# Sheet2.net
KiCad netlist of a schematic drawn in Altium Designer
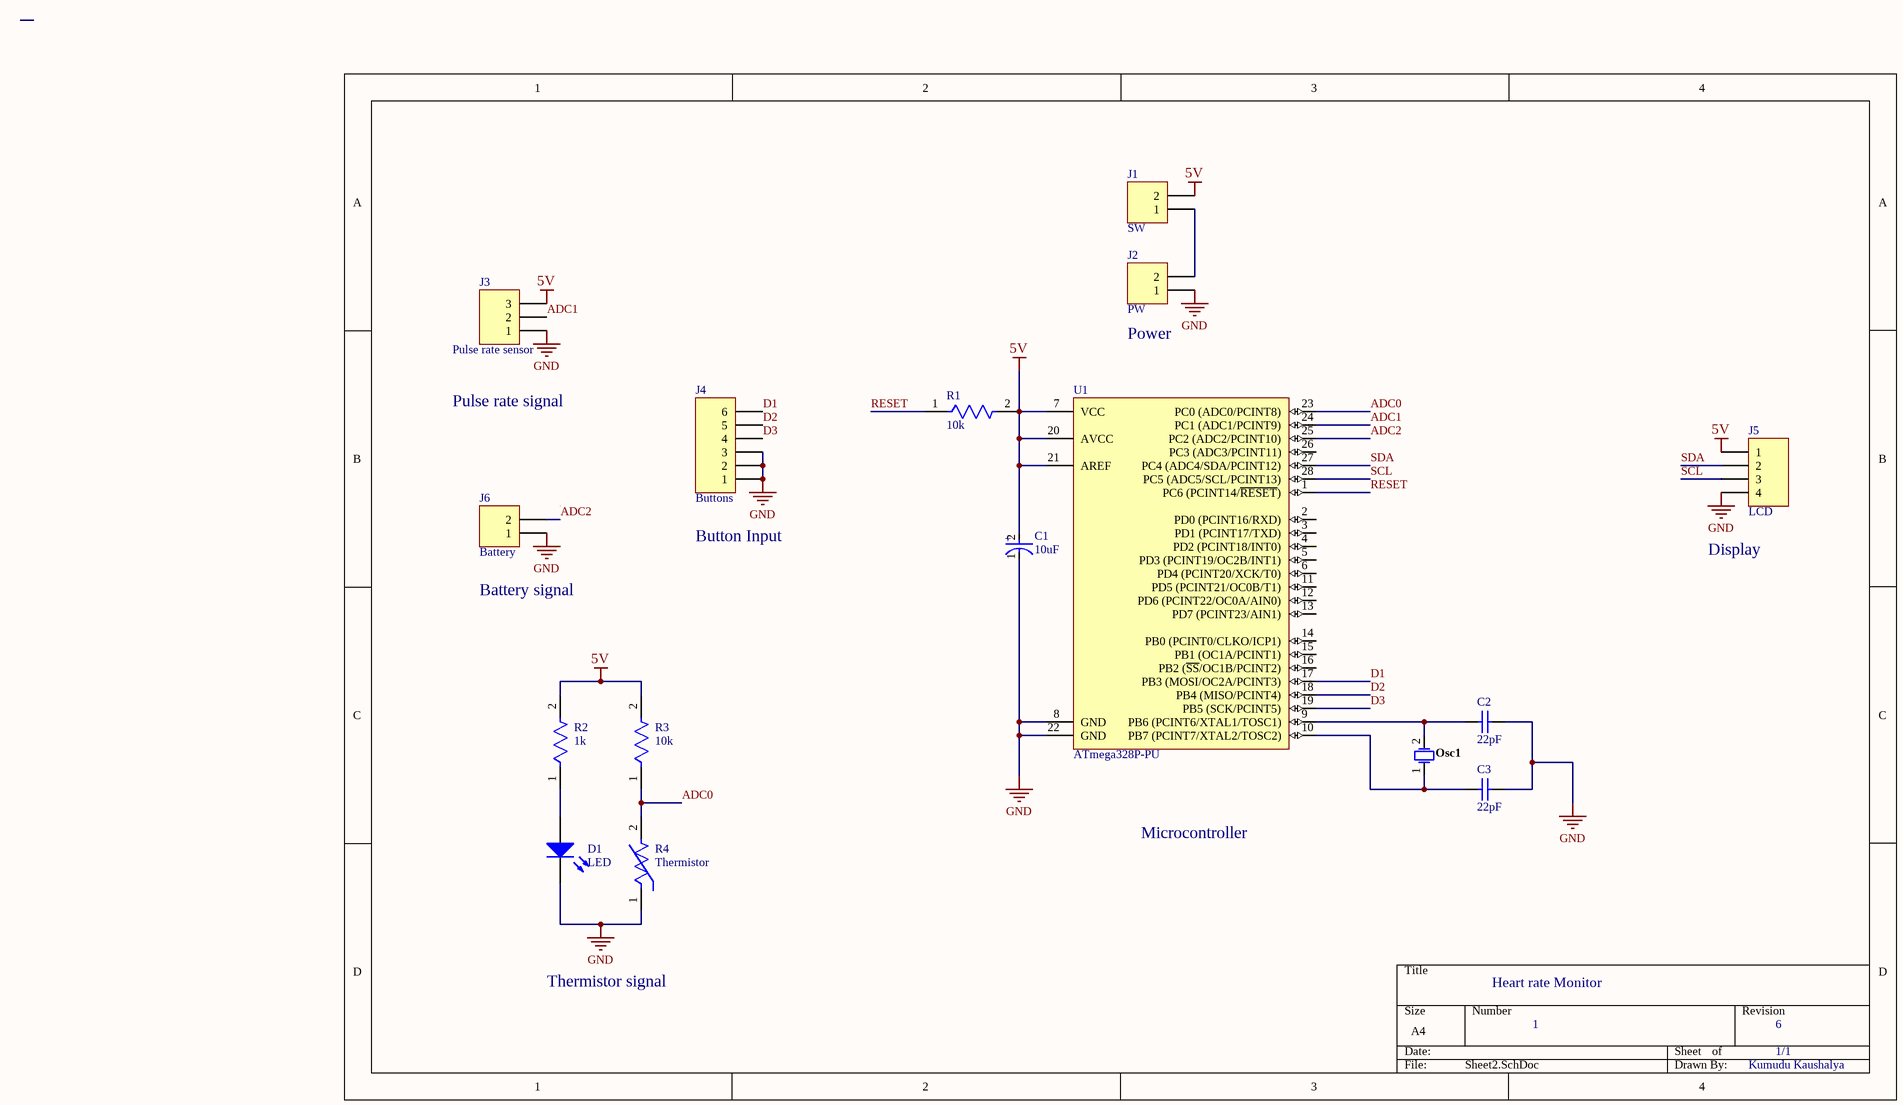
[diagram p0: Sheet2.SchDoc]

(export (version "E")
  (design (tool "Eeschema 10.0.6"))
  (components
    (comp (ref "C1")
      (value "10uF")
      (footprint "FP-RAD-TH-D_5_0_5-L_11_1-MFG")
      (description "Aluminum Electrolytic Capacitors (Radial Lead Type) 10uF ±20% 100V")
      (fields (field (name "VOLTAGE") "100V") (field (name "TOLERANCE") "20%"))
      (libsource (lib "Altium Content Vault") (part "a00bbbee19879c290e62620ae7e47b1"))
    )
    (comp (ref "C2")
      (value "22pF")
      (footprint "KEMT-C315-THT-2")
      (description "Capacitor, Ceramic, 22 pF, +/-10 %, 100 V, -55 to 125 degC, 2-Pin THD, RoHS, Bulk")
      (libsource (lib "Altium Content Vault") (part "CAP-NP-2"))
    )
    (comp (ref "C3")
      (value "22pF")
      (footprint "KEMT-C315-THT-2")
      (description "Capacitor, Ceramic, 22 pF, +/-10 %, 100 V, -55 to 125 degC, 2-Pin THD, RoHS, Bulk")
      (libsource (lib "Altium Content Vault") (part "CAP-NP-2"))
    )
    (comp (ref "D1")
      (value "LED")
      (footprint "LED-1")
      (description "Typical RED GaAs LED")
      (fields (field (name "PUBLISHER") "Altium Limited"))
      (libsource (lib "Miscellaneous Devices") (part "LED1"))
    )
    (comp (ref "J1")
      (value "SW")
      (footprint "HDR1X2")
      (description "Header, 2-Pin")
      (fields (field (name "PUBLISHER") "Altium Limited"))
      (libsource (lib "Miscellaneous Connectors") (part "Header 2"))
    )
    (comp (ref "J2")
      (value "PW")
      (footprint "HDR1X2")
      (description "Header, 2-Pin")
      (fields (field (name "PUBLISHER") "Altium Limited"))
      (libsource (lib "Miscellaneous Connectors") (part "Header 2"))
    )
    (comp (ref "J3")
      (value "Pulse rate sensor")
      (footprint "HDR1X3")
      (description "Header, 3-Pin")
      (fields (field (name "PUBLISHER") "Altium Limited"))
      (libsource (lib "Miscellaneous Connectors") (part "Header 3"))
    )
    (comp (ref "J4")
      (value "Buttons")
      (footprint "HDR1X6")
      (description "Header, 6-Pin")
      (fields (field (name "PUBLISHER") "Altium Limited"))
      (libsource (lib "Miscellaneous Connectors") (part "Header 6"))
    )
    (comp (ref "J5")
      (value "LCD")
      (footprint "HDR1X4")
      (description "Header, 4-Pin")
      (fields (field (name "PUBLISHER") "Altium Limited"))
      (libsource (lib "Miscellaneous Connectors") (part "Header 4"))
    )
    (comp (ref "J6")
      (value "Battery")
      (footprint "HDR1X2")
      (description "Header, 2-Pin")
      (fields (field (name "PUBLISHER") "Altium Limited"))
      (libsource (lib "Miscellaneous Connectors") (part "Header 2"))
    )
    (comp (ref "Osc1")
      (value "Osc1")
      (footprint "FOX-FOXSLF160-20")
      (description "Resistance Weld Thru-Hole Crystal, 16 MHz, -20 to 70 degC, 2-Pin THD, RoHS, Bulk")
      (fields (field (name "TOLERANCE") "1%"))
      (libsource (lib "Altium Content Vault") (part "XTAL-1-2-2"))
    )
    (comp (ref "R1")
      (value "10k")
      (footprint "FP-MBB0207-MFG")
      (description "RES 10K OHM 0.6W 1% AXIAL")
      (fields (field (name "TOLERANCE") "1%"))
      (libsource (lib "Altium Content Vault") (part "1029c3af85768c4190bb7ad29bc67b5"))
    )
    (comp (ref "R2")
      (value "1k")
      (footprint "FP-MRS25-MFG")
      (description "RES 1K OHM 0.6W 1% AXIAL")
      (fields (field (name "TOLERANCE") "1%"))
      (libsource (lib "Altium Content Vault") (part "1029c3af85768c4190bb7ad29bc67b5"))
    )
    (comp (ref "R3")
      (value "10k")
      (footprint "FP-MBB0207-MFG")
      (description "RES 10K OHM 0.6W 1% AXIAL")
      (fields (field (name "TOLERANCE") "1%"))
      (libsource (lib "Altium Content Vault") (part "1029c3af85768c4190bb7ad29bc67b5"))
    )
    (comp (ref "R4")
      (value "Thermistor")
      (footprint "FP-NTCLE100E3104JB0-MFG")
      (description "NTC THERMISTOR 100K OHM 5% BEAD")
      (fields (field (name "TOLERANCE") "5%"))
      (libsource (lib "Altium Content Vault") (part "3b148a6ebabc5fb4d708a66c052d352"))
    )
    (comp (ref "U1")
      (value "ATmega328P-PU")
      (footprint "28P3")
      (libsource (lib "Altium Content Vault") (part "MC-8B-ATM48-IL28"))
    )
  )
  (nets
    (net (code "1") (name "/ADC0") (class "Default")
      (node (ref "R3") (pin "1") (pinfunction "1_1") (pintype "passive"))
      (node (ref "R4") (pin "2") (pinfunction "2_2") (pintype "passive"))
      (node (ref "U1") (pin "23") (pinfunction "PC0_(ADC0/PCINT8)_23") (pintype "bidirectional"))
    )
    (net (code "2") (name "/ADC1") (class "Default")
      (node (ref "J3") (pin "2") (pinfunction "2_2") (pintype "passive"))
      (node (ref "U1") (pin "24") (pinfunction "PC1_(ADC1/PCINT9)_24") (pintype "bidirectional"))
    )
    (net (code "3") (name "/ADC2") (class "Default")
      (node (ref "J6") (pin "2") (pinfunction "2_2") (pintype "passive"))
      (node (ref "U1") (pin "25") (pinfunction "PC2_(ADC2/PCINT10)_25") (pintype "bidirectional"))
    )
    (net (code "4") (name "/D1") (class "Default")
      (node (ref "J4") (pin "6") (pinfunction "6_6") (pintype "passive"))
      (node (ref "U1") (pin "17") (pinfunction "PB3_(MOSI/OC2A/PCINT3)_17") (pintype "bidirectional"))
    )
    (net (code "5") (name "/D2") (class "Default")
      (node (ref "J4") (pin "5") (pinfunction "5_5") (pintype "passive"))
      (node (ref "U1") (pin "18") (pinfunction "PB4_(MISO/PCINT4)_18") (pintype "bidirectional"))
    )
    (net (code "6") (name "/D3") (class "Default")
      (node (ref "J4") (pin "4") (pinfunction "4_4") (pintype "passive"))
      (node (ref "U1") (pin "19") (pinfunction "PB5_(SCK/PCINT5)_19") (pintype "bidirectional"))
    )
    (net (code "7") (name "/RESET") (class "Default")
      (node (ref "R1") (pin "1") (pinfunction "1_1") (pintype "passive"))
      (node (ref "U1") (pin "1") (pinfunction "PC6_(PCINT14/~{RESET})_1") (pintype "bidirectional"))
    )
    (net (code "8") (name "/SCL") (class "Default")
      (node (ref "J5") (pin "3") (pinfunction "3_3") (pintype "passive"))
      (node (ref "U1") (pin "28") (pinfunction "PC5_(ADC5/SCL/PCINT13)_28") (pintype "bidirectional"))
    )
    (net (code "9") (name "/SDA") (class "Default")
      (node (ref "J5") (pin "2") (pinfunction "2_2") (pintype "passive"))
      (node (ref "U1") (pin "27") (pinfunction "PC4_(ADC4/SDA/PCINT12)_27") (pintype "bidirectional"))
    )
    (net (code "10") (name "5V") (class "Default")
      (node (ref "C1") (pin "2") (pinfunction "A_2") (pintype "passive"))
      (node (ref "J1") (pin "2") (pinfunction "2_2") (pintype "passive"))
      (node (ref "J3") (pin "3") (pinfunction "3_3") (pintype "passive"))
      (node (ref "J5") (pin "1") (pinfunction "1_1") (pintype "passive"))
      (node (ref "R1") (pin "2") (pinfunction "2_2") (pintype "passive"))
      (node (ref "R2") (pin "2") (pinfunction "2_2") (pintype "passive"))
      (node (ref "R3") (pin "2") (pinfunction "2_2") (pintype "passive"))
      (node (ref "U1") (pin "20") (pinfunction "AVCC_20") (pintype "power_in"))
      (node (ref "U1") (pin "21") (pinfunction "AREF_21") (pintype "power_in"))
      (node (ref "U1") (pin "7") (pinfunction "VCC_7") (pintype "power_in"))
    )
    (net (code "11") (name "GND") (class "Default")
      (node (ref "C1") (pin "1") (pinfunction "C_1") (pintype "passive"))
      (node (ref "C2") (pin "2") (pinfunction "2_2") (pintype "passive"))
      (node (ref "C3") (pin "2") (pinfunction "2_2") (pintype "passive"))
      (node (ref "D1") (pin "2") (pinfunction "K_2") (pintype "passive"))
      (node (ref "J2") (pin "1") (pinfunction "1_1") (pintype "passive"))
      (node (ref "J3") (pin "1") (pinfunction "1_1") (pintype "passive"))
      (node (ref "J4") (pin "1") (pinfunction "1_1") (pintype "passive"))
      (node (ref "J4") (pin "2") (pinfunction "2_2") (pintype "passive"))
      (node (ref "J4") (pin "3") (pinfunction "3_3") (pintype "passive"))
      (node (ref "J5") (pin "4") (pinfunction "4_4") (pintype "passive"))
      (node (ref "J6") (pin "1") (pinfunction "1_1") (pintype "passive"))
      (node (ref "R4") (pin "1") (pinfunction "1_1") (pintype "passive"))
      (node (ref "U1") (pin "22") (pinfunction "GND_22") (pintype "power_in"))
      (node (ref "U1") (pin "8") (pinfunction "GND_8") (pintype "power_in"))
    )
    (net (code "12") (name "Net-(D1-A)") (class "Default")
      (node (ref "D1") (pin "1") (pinfunction "A_1") (pintype "passive"))
      (node (ref "R2") (pin "1") (pinfunction "1_1") (pintype "passive"))
    )
    (net (code "13") (name "Net-(J1-Pad1)") (class "Default")
      (node (ref "J1") (pin "1") (pinfunction "1_1") (pintype "passive"))
      (node (ref "J2") (pin "2") (pinfunction "2_2") (pintype "passive"))
    )
    (net (code "14") (name "Net-(U1-PB6_(PCINT6{slash}XTAL1{slash}TOSC1))") (class "Default")
      (node (ref "C2") (pin "1") (pinfunction "1_1") (pintype "passive"))
      (node (ref "Osc1") (pin "2") (pinfunction "2_2") (pintype "passive"))
      (node (ref "U1") (pin "9") (pinfunction "PB6_(PCINT6/XTAL1/TOSC1)_9") (pintype "bidirectional"))
    )
    (net (code "15") (name "Net-(U1-PB7_(PCINT7{slash}XTAL2{slash}TOSC2))") (class "Default")
      (node (ref "C3") (pin "1") (pinfunction "1_1") (pintype "passive"))
      (node (ref "Osc1") (pin "1") (pinfunction "1_1") (pintype "passive"))
      (node (ref "U1") (pin "10") (pinfunction "PB7_(PCINT7/XTAL2/TOSC2)_10") (pintype "bidirectional"))
    )
    (net (code "16") (name "unconnected-(U1-PB0_(PCINT0{slash}CLKO{slash}ICP1)-Pad14)") (class "Default")
      (node (ref "U1") (pin "14") (pinfunction "PB0_(PCINT0/CLKO/ICP1)_14") (pintype "bidirectional"))
    )
    (net (code "17") (name "unconnected-(U1-PB1_(OC1A{slash}PCINT1)-Pad15)") (class "Default")
      (node (ref "U1") (pin "15") (pinfunction "PB1_(OC1A/PCINT1)_15") (pintype "bidirectional"))
    )
    (net (code "18") (name "unconnected-(U1-PB2_(~{SS}{slash}OC1B{slash}PCINT2)-Pad16)") (class "Default")
      (node (ref "U1") (pin "16") (pinfunction "PB2_(~{SS}/OC1B/PCINT2)_16") (pintype "bidirectional"))
    )
    (net (code "19") (name "unconnected-(U1-PC3_(ADC3{slash}PCINT11)-Pad26)") (class "Default")
      (node (ref "U1") (pin "26") (pinfunction "PC3_(ADC3/PCINT11)_26") (pintype "bidirectional"))
    )
    (net (code "20") (name "unconnected-(U1-PD0_(PCINT16{slash}RXD)-Pad2)") (class "Default")
      (node (ref "U1") (pin "2") (pinfunction "PD0_(PCINT16/RXD)_2") (pintype "bidirectional"))
    )
    (net (code "21") (name "unconnected-(U1-PD1_(PCINT17{slash}TXD)-Pad3)") (class "Default")
      (node (ref "U1") (pin "3") (pinfunction "PD1_(PCINT17/TXD)_3") (pintype "bidirectional"))
    )
    (net (code "22") (name "unconnected-(U1-PD2_(PCINT18{slash}INT0)-Pad4)") (class "Default")
      (node (ref "U1") (pin "4") (pinfunction "PD2_(PCINT18/INT0)_4") (pintype "bidirectional"))
    )
    (net (code "23") (name "unconnected-(U1-PD3_(PCINT19{slash}OC2B{slash}INT1)-Pad5)") (class "Default")
      (node (ref "U1") (pin "5") (pinfunction "PD3_(PCINT19/OC2B/INT1)_5") (pintype "bidirectional"))
    )
    (net (code "24") (name "unconnected-(U1-PD4_(PCINT20{slash}XCK{slash}T0)-Pad6)") (class "Default")
      (node (ref "U1") (pin "6") (pinfunction "PD4_(PCINT20/XCK/T0)_6") (pintype "bidirectional"))
    )
    (net (code "25") (name "unconnected-(U1-PD5_(PCINT21{slash}OC0B{slash}T1)-Pad11)") (class "Default")
      (node (ref "U1") (pin "11") (pinfunction "PD5_(PCINT21/OC0B/T1)_11") (pintype "bidirectional"))
    )
    (net (code "26") (name "unconnected-(U1-PD6_(PCINT22{slash}OC0A{slash}AIN0)-Pad12)") (class "Default")
      (node (ref "U1") (pin "12") (pinfunction "PD6_(PCINT22/OC0A/AIN0)_12") (pintype "bidirectional"))
    )
    (net (code "27") (name "unconnected-(U1-PD7_(PCINT23{slash}AIN1)-Pad13)") (class "Default")
      (node (ref "U1") (pin "13") (pinfunction "PD7_(PCINT23/AIN1)_13") (pintype "bidirectional"))
    )
  )
)
